# Arduino.net
KiCad netlist of a schematic drawn in Altium Designer
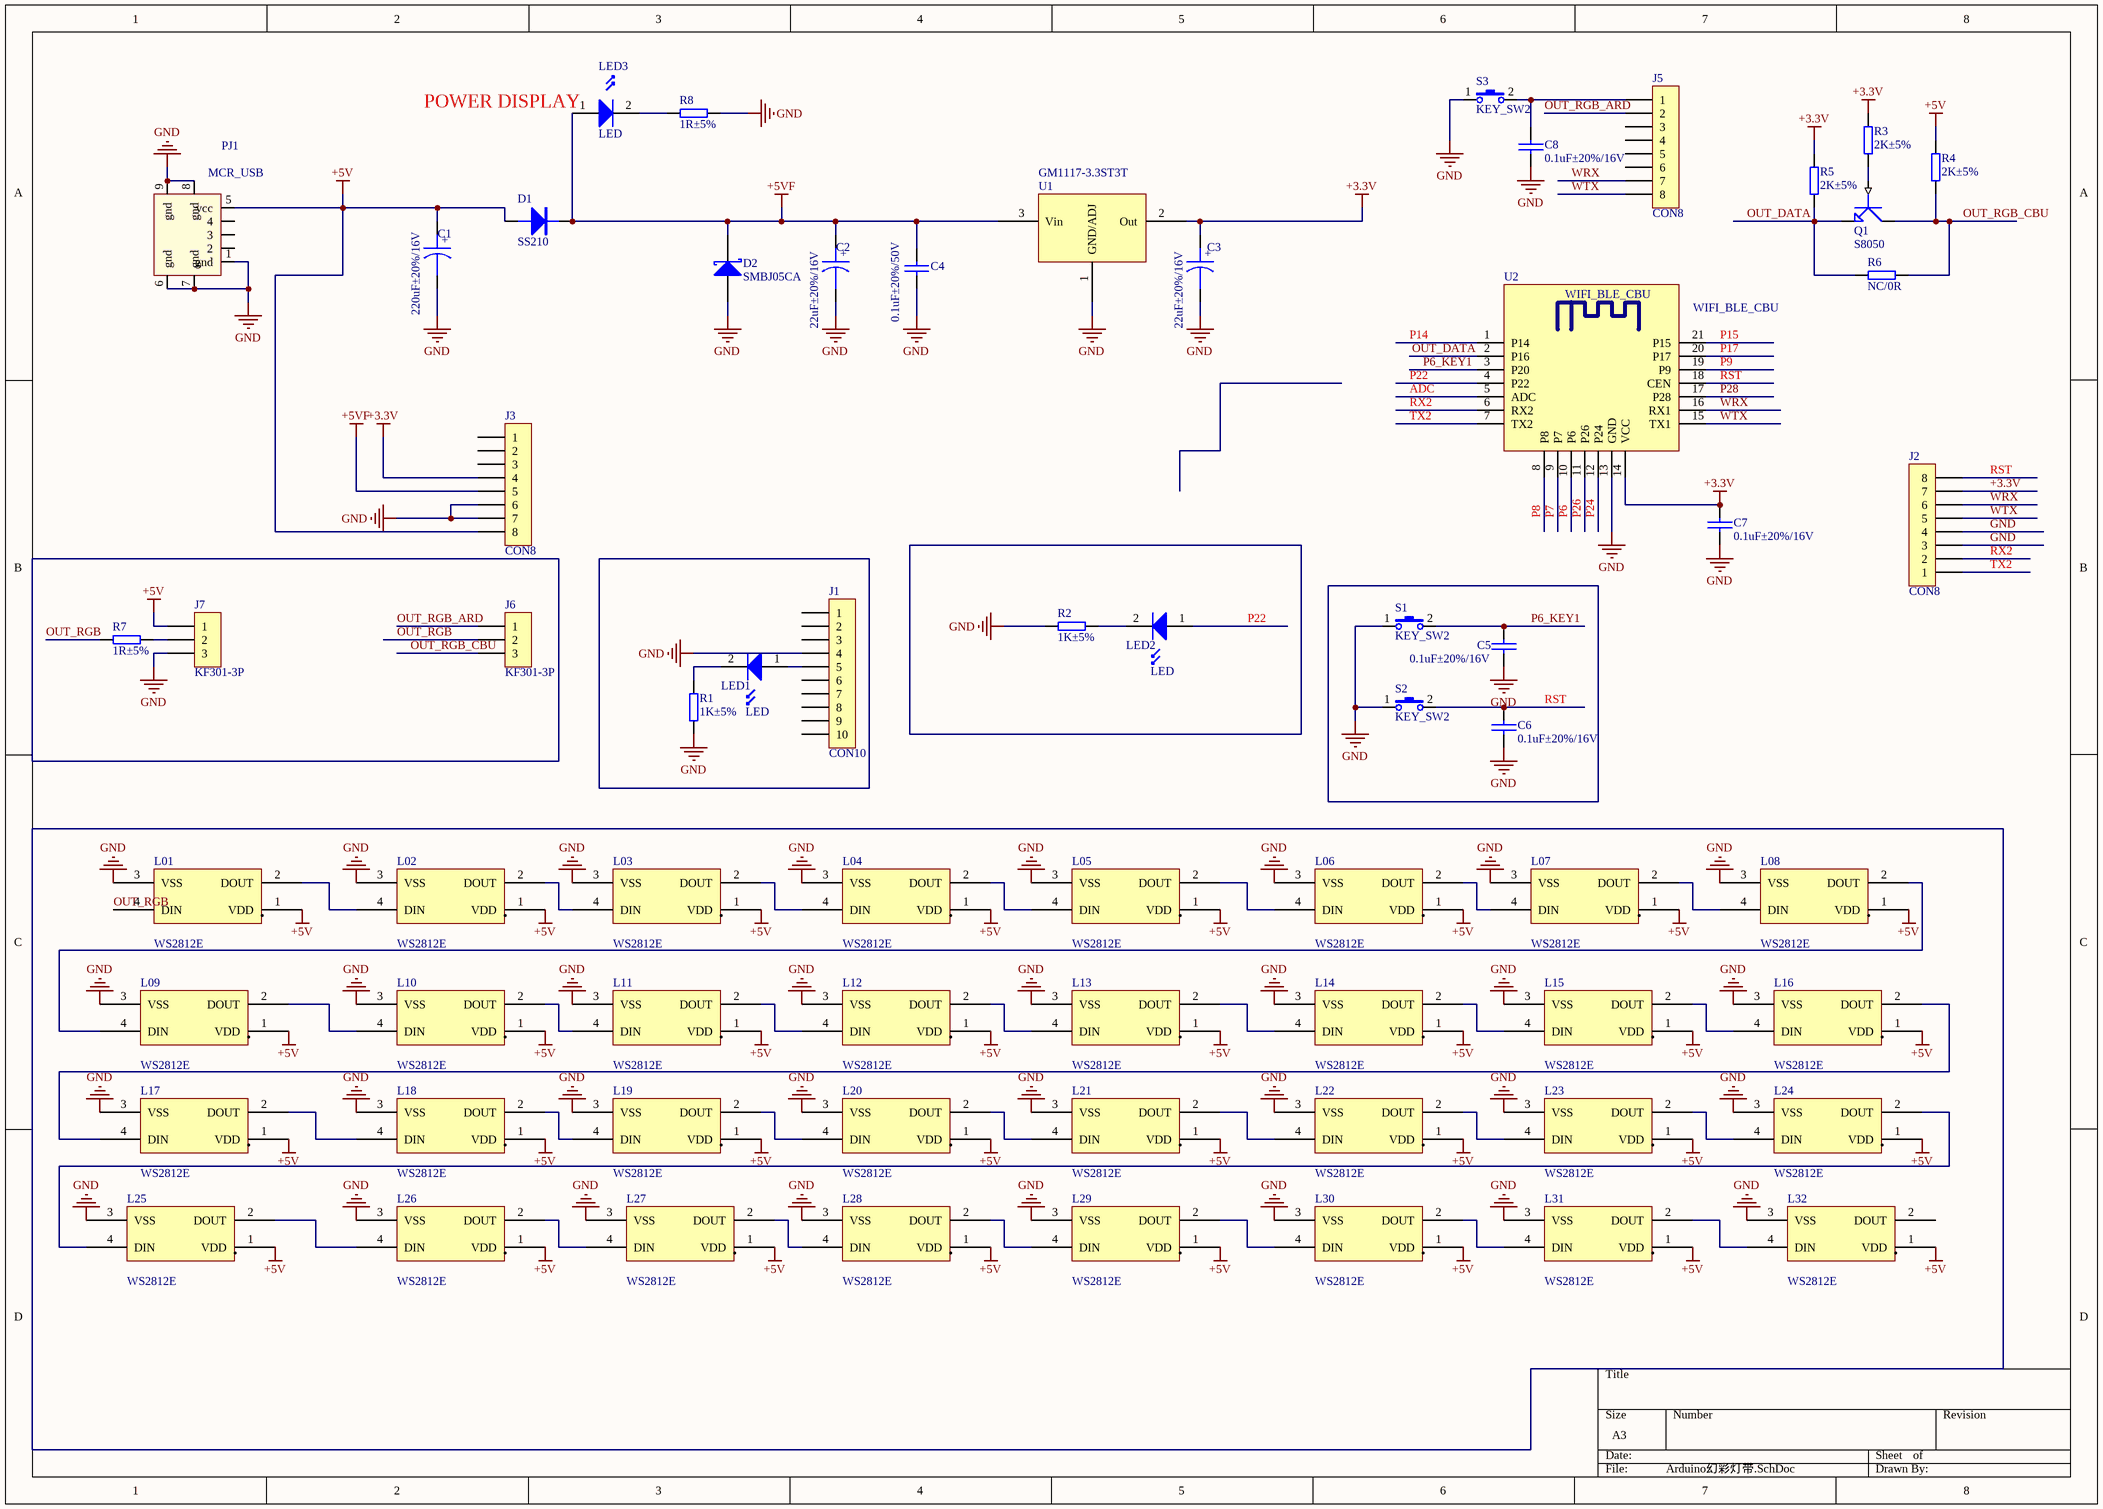
[diagram p0: Arduino幻彩灯带.SchDoc]

(export (version "E")
  (design (tool "Eeschema 10.0.6"))
  (components
    (comp (ref "C1")
      (value "220uF±20%/16V")
      (footprint "钽电容B3528")
      (description "Capacitor")
      (libsource (lib "*") (part "CAPACITOR POL"))
    )
    (comp (ref "C2")
      (value "22uF±20%/16V")
      (footprint "钽电容B3528")
      (description "Capacitor")
      (libsource (lib "*") (part "CAPACITOR POL"))
    )
    (comp (ref "C3")
      (value "22uF±20%/16V")
      (footprint "钽电容B3528")
      (description "Capacitor")
      (libsource (lib "*") (part "CAPACITOR POL"))
    )
    (comp (ref "C4")
      (value "0.1uF±20%/50V")
      (footprint "C0603")
      (description "Capacitor")
      (libsource (lib "昊华元件库sch") (part "CAP"))
    )
    (comp (ref "C5")
      (value "0.1uF±20%/16V")
      (footprint "C0603")
      (description "Capacitor")
      (libsource (lib "昊华元件库sch") (part "CAP"))
    )
    (comp (ref "C6")
      (value "0.1uF±20%/16V")
      (footprint "C0603")
      (description "Capacitor")
      (libsource (lib "昊华元件库sch") (part "CAP"))
    )
    (comp (ref "C7")
      (value "0.1uF±20%/16V")
      (footprint "C0603")
      (description "Capacitor")
      (libsource (lib "昊华元件库sch") (part "CAP"))
    )
    (comp (ref "C8")
      (value "0.1uF±20%/16V")
      (footprint "C0603")
      (description "Capacitor")
      (libsource (lib "昊华元件库sch") (part "CAP"))
    )
    (comp (ref "D1")
      (value "SS210")
      (footprint "SMA(DO-214AC)")
      (description "Diode")
      (libsource (lib "小马元件库sch") (part "Diode1"))
    )
    (comp (ref "D2")
      (value "SMBJ05CA")
      (footprint "SMB(DO-214AA)")
      (description "Schottky Diode")
      (fields (field (name "MFR") "Toshiba"))
      (libsource (lib "Miscellaneous Devices") (part "D Schottky"))
    )
    (comp (ref "J1")
      (value "CON10")
      (footprint "HDR1X10Z")
      (description "Connector")
      (libsource (lib "小马元件库sch") (part "CON10"))
    )
    (comp (ref "J2")
      (value "CON8")
      (footprint "HDR1X8Z")
      (description "Connector")
      (libsource (lib "") (part "CON8_1"))
    )
    (comp (ref "J3")
      (value "CON8")
      (footprint "HDR1X8Z")
      (description "Connector")
      (libsource (lib "小马元件库sch") (part "CON8"))
    )
    (comp (ref "J5")
      (value "CON8")
      (footprint "HDR1X8Z")
      (description "Connector")
      (libsource (lib "小马元件库sch") (part "CON8"))
    )
    (comp (ref "J6")
      (value "KF301-3P")
      (footprint "SIP3 - 2.54")
      (description "Connector")
      (libsource (lib "小马元件库sch") (part "CON3"))
    )
    (comp (ref "J7")
      (value "KF301-3P")
      (footprint "SIP3 - 2.54")
      (description "Connector")
      (libsource (lib "小马元件库sch") (part "CON3"))
    )
    (comp (ref "L01") (value "WS2812E") (footprint "WS2812E") (libsource (lib "WS2812E") (part "WS2812E")))
    (comp (ref "L02") (value "WS2812E") (footprint "WS2812E") (libsource (lib "WS2812E") (part "WS2812E")))
    (comp (ref "L03") (value "WS2812E") (footprint "WS2812E") (libsource (lib "WS2812E") (part "WS2812E")))
    (comp (ref "L04") (value "WS2812E") (footprint "WS2812E") (libsource (lib "WS2812E") (part "WS2812E")))
    (comp (ref "L05") (value "WS2812E") (footprint "WS2812E") (libsource (lib "WS2812E") (part "WS2812E")))
    (comp (ref "L06") (value "WS2812E") (footprint "WS2812E") (libsource (lib "WS2812E") (part "WS2812E")))
    (comp (ref "L07") (value "WS2812E") (footprint "WS2812E") (libsource (lib "WS2812E") (part "WS2812E")))
    (comp (ref "L08") (value "WS2812E") (footprint "WS2812E") (libsource (lib "WS2812E") (part "WS2812E")))
    (comp (ref "L09") (value "WS2812E") (footprint "WS2812E") (libsource (lib "WS2812E") (part "WS2812E")))
    (comp (ref "L10") (value "WS2812E") (footprint "WS2812E") (libsource (lib "WS2812E") (part "WS2812E")))
    (comp (ref "L11") (value "WS2812E") (footprint "WS2812E") (libsource (lib "WS2812E") (part "WS2812E")))
    (comp (ref "L12") (value "WS2812E") (footprint "WS2812E") (libsource (lib "WS2812E") (part "WS2812E")))
    (comp (ref "L13") (value "WS2812E") (footprint "WS2812E") (libsource (lib "WS2812E") (part "WS2812E")))
    (comp (ref "L14") (value "WS2812E") (footprint "WS2812E") (libsource (lib "WS2812E") (part "WS2812E")))
    (comp (ref "L15") (value "WS2812E") (footprint "WS2812E") (libsource (lib "WS2812E") (part "WS2812E")))
    (comp (ref "L16") (value "WS2812E") (footprint "WS2812E") (libsource (lib "WS2812E") (part "WS2812E")))
    (comp (ref "L17") (value "WS2812E") (footprint "WS2812E") (libsource (lib "WS2812E") (part "WS2812E")))
    (comp (ref "L18") (value "WS2812E") (footprint "WS2812E") (libsource (lib "WS2812E") (part "WS2812E")))
    (comp (ref "L19") (value "WS2812E") (footprint "WS2812E") (libsource (lib "WS2812E") (part "WS2812E")))
    (comp (ref "L20") (value "WS2812E") (footprint "WS2812E") (libsource (lib "WS2812E") (part "WS2812E")))
    (comp (ref "L21") (value "WS2812E") (footprint "WS2812E") (libsource (lib "WS2812E") (part "WS2812E")))
    (comp (ref "L22") (value "WS2812E") (footprint "WS2812E") (libsource (lib "WS2812E") (part "WS2812E")))
    (comp (ref "L23") (value "WS2812E") (footprint "WS2812E") (libsource (lib "WS2812E") (part "WS2812E")))
    (comp (ref "L24") (value "WS2812E") (footprint "WS2812E") (libsource (lib "WS2812E") (part "WS2812E")))
    (comp (ref "L25") (value "WS2812E") (footprint "WS2812E") (libsource (lib "WS2812E") (part "WS2812E")))
    (comp (ref "L26") (value "WS2812E") (footprint "WS2812E") (libsource (lib "WS2812E") (part "WS2812E")))
    (comp (ref "L27") (value "WS2812E") (footprint "WS2812E") (libsource (lib "WS2812E") (part "WS2812E")))
    (comp (ref "L28") (value "WS2812E") (footprint "WS2812E") (libsource (lib "WS2812E") (part "WS2812E")))
    (comp (ref "L29") (value "WS2812E") (footprint "WS2812E") (libsource (lib "WS2812E") (part "WS2812E")))
    (comp (ref "L30") (value "WS2812E") (footprint "WS2812E") (libsource (lib "WS2812E") (part "WS2812E")))
    (comp (ref "L31") (value "WS2812E") (footprint "WS2812E") (libsource (lib "WS2812E") (part "WS2812E")))
    (comp (ref "L32") (value "WS2812E") (footprint "WS2812E") (libsource (lib "WS2812E") (part "WS2812E")))
    (comp (ref "LED1")
      (value "LED")
      (footprint "LED0805_1")
      (fields (field (name "PUBLISHER") "*"))
      (libsource (lib "小马元件库sch") (part "LED"))
    )
    (comp (ref "LED2")
      (value "LED")
      (footprint "LED0805_1")
      (fields (field (name "PUBLISHER") "*"))
      (libsource (lib "小马元件库sch") (part "LED"))
    )
    (comp (ref "LED3")
      (value "LED")
      (footprint "LED0805_1")
      (fields (field (name "PUBLISHER") "*"))
      (libsource (lib "小马元件库sch") (part "LED"))
    )
    (comp (ref "PJ1")
      (value "MCR_USB")
      (footprint "MICRO_USB-NEW-16.12.12")
      (fields (field (name "PUBLISHER") "*"))
      (libsource (lib "昊华元件库sch") (part "MCR_USB"))
    )
    (comp (ref "Q1")
      (value "S8050")
      (footprint "SOT-23-NPN")
      (description "NPN Transistor")
      (libsource (lib "小马元件库sch") (part "NPN"))
    )
    (comp (ref "R1") (value "1K±5%") (footprint "R0603") (libsource (lib "昊华元件库sch") (part "RES5")))
    (comp (ref "R2") (value "1K±5%") (footprint "R0603") (libsource (lib "昊华元件库sch") (part "RES5")))
    (comp (ref "R3") (value "2K±5%") (footprint "R0603") (libsource (lib "昊华元件库sch") (part "RES5")))
    (comp (ref "R4") (value "2K±5%") (footprint "R0603") (libsource (lib "昊华元件库sch") (part "RES5")))
    (comp (ref "R5") (value "2K±5%") (footprint "R0603") (libsource (lib "昊华元件库sch") (part "RES5")))
    (comp (ref "R6") (value "NC/0R") (footprint "R0603") (libsource (lib "昊华元件库sch") (part "RES5")))
    (comp (ref "R7") (value "1R±5%") (footprint "R0603") (libsource (lib "昊华元件库sch") (part "RES5")))
    (comp (ref "R8") (value "1R±5%") (footprint "R0603") (libsource (lib "昊华元件库sch") (part "RES5")))
    (comp (ref "S1") (value "KEY_SW2") (footprint "KEY4-SMD") (libsource (lib "小马元件库sch") (part "KEY_SW2")))
    (comp (ref "S2") (value "KEY_SW2") (footprint "KEY4-SMD") (libsource (lib "小马元件库sch") (part "KEY_SW2")))
    (comp (ref "S3") (value "KEY_SW2") (footprint "KEY4-SMD") (libsource (lib "小马元件库sch") (part "KEY_SW2")))
    (comp (ref "U1") (value "GM1117-3.3ST3T") (footprint "SOT-223") (libsource (lib "mylib") (part "GM1117")))
    (comp (ref "U2")
      (value "WIFI_BLE_CBU")
      (footprint "WIFI_BLE_CBU")
      (description "Module")
      (libsource (lib "TYModeSchlib V03") (part "WIFI_BLE_CBU"))
    )
  )
  (nets
    (net (code "1") (name "+3.3V") (class "Default")
      (node (ref "C3") (pin "1") (pinfunction "1_1") (pintype "passive"))
      (node (ref "C7") (pin "2") (pinfunction "2_2") (pintype "passive"))
      (node (ref "J2") (pin "7") (pinfunction "7_7") (pintype "passive"))
      (node (ref "J3") (pin "4") (pinfunction "4_4") (pintype "passive"))
      (node (ref "R3") (pin "1") (pinfunction "1_1") (pintype "passive"))
      (node (ref "R5") (pin "1") (pinfunction "1_1") (pintype "passive"))
      (node (ref "U1") (pin "2") (pinfunction "Out_2") (pintype "passive"))
      (node (ref "U2") (pin "14") (pinfunction "VCC_14") (pintype "passive"))
    )
    (net (code "2") (name "+5V") (class "Default")
      (node (ref "C1") (pin "1") (pinfunction "1_1") (pintype "passive"))
      (node (ref "D1") (pin "1") (pinfunction "1_1") (pintype "passive"))
      (node (ref "J3") (pin "8") (pinfunction "8_8") (pintype "passive"))
      (node (ref "J7") (pin "1") (pinfunction "1_1") (pintype "passive"))
      (node (ref "L01") (pin "1") (pinfunction "VDD_1") (pintype "passive"))
      (node (ref "L02") (pin "1") (pinfunction "VDD_1") (pintype "passive"))
      (node (ref "L03") (pin "1") (pinfunction "VDD_1") (pintype "passive"))
      (node (ref "L04") (pin "1") (pinfunction "VDD_1") (pintype "passive"))
      (node (ref "L05") (pin "1") (pinfunction "VDD_1") (pintype "passive"))
      (node (ref "L06") (pin "1") (pinfunction "VDD_1") (pintype "passive"))
      (node (ref "L07") (pin "1") (pinfunction "VDD_1") (pintype "passive"))
      (node (ref "L08") (pin "1") (pinfunction "VDD_1") (pintype "passive"))
      (node (ref "L09") (pin "1") (pinfunction "VDD_1") (pintype "passive"))
      (node (ref "L10") (pin "1") (pinfunction "VDD_1") (pintype "passive"))
      (node (ref "L11") (pin "1") (pinfunction "VDD_1") (pintype "passive"))
      (node (ref "L12") (pin "1") (pinfunction "VDD_1") (pintype "passive"))
      (node (ref "L13") (pin "1") (pinfunction "VDD_1") (pintype "passive"))
      (node (ref "L14") (pin "1") (pinfunction "VDD_1") (pintype "passive"))
      (node (ref "L15") (pin "1") (pinfunction "VDD_1") (pintype "passive"))
      (node (ref "L16") (pin "1") (pinfunction "VDD_1") (pintype "passive"))
      (node (ref "L17") (pin "1") (pinfunction "VDD_1") (pintype "passive"))
      (node (ref "L18") (pin "1") (pinfunction "VDD_1") (pintype "passive"))
      (node (ref "L19") (pin "1") (pinfunction "VDD_1") (pintype "passive"))
      (node (ref "L20") (pin "1") (pinfunction "VDD_1") (pintype "passive"))
      (node (ref "L21") (pin "1") (pinfunction "VDD_1") (pintype "passive"))
      (node (ref "L22") (pin "1") (pinfunction "VDD_1") (pintype "passive"))
      (node (ref "L23") (pin "1") (pinfunction "VDD_1") (pintype "passive"))
      (node (ref "L24") (pin "1") (pinfunction "VDD_1") (pintype "passive"))
      (node (ref "L25") (pin "1") (pinfunction "VDD_1") (pintype "passive"))
      (node (ref "L26") (pin "1") (pinfunction "VDD_1") (pintype "passive"))
      (node (ref "L27") (pin "1") (pinfunction "VDD_1") (pintype "passive"))
      (node (ref "L28") (pin "1") (pinfunction "VDD_1") (pintype "passive"))
      (node (ref "L29") (pin "1") (pinfunction "VDD_1") (pintype "passive"))
      (node (ref "L30") (pin "1") (pinfunction "VDD_1") (pintype "passive"))
      (node (ref "L31") (pin "1") (pinfunction "VDD_1") (pintype "passive"))
      (node (ref "L32") (pin "1") (pinfunction "VDD_1") (pintype "passive"))
      (node (ref "PJ1") (pin "5") (pinfunction "vcc_5") (pintype "passive"))
      (node (ref "R4") (pin "1") (pinfunction "1_1") (pintype "passive"))
    )
    (net (code "3") (name "+5VF") (class "Default")
      (node (ref "C2") (pin "1") (pinfunction "1_1") (pintype "passive"))
      (node (ref "C4") (pin "1") (pinfunction "1_1") (pintype "passive"))
      (node (ref "D1") (pin "2") (pinfunction "2_2") (pintype "passive"))
      (node (ref "D2") (pin "2") (pinfunction "K_2") (pintype "passive"))
      (node (ref "J3") (pin "5") (pinfunction "5_5") (pintype "passive"))
      (node (ref "LED3") (pin "1") (pinfunction "1_1") (pintype "passive"))
      (node (ref "U1") (pin "3") (pinfunction "Vin_3") (pintype "passive"))
    )
    (net (code "4") (name "/ADC") (class "Default")
      (node (ref "U2") (pin "5") (pinfunction "ADC_5") (pintype "passive"))
    )
    (net (code "5") (name "/OUT_DATA") (class "Default")
      (node (ref "Q1") (pin "1") (pinfunction "E_1") (pintype "passive"))
      (node (ref "R5") (pin "2") (pinfunction "2_2") (pintype "passive"))
      (node (ref "R6") (pin "1") (pinfunction "1_1") (pintype "passive"))
      (node (ref "U2") (pin "2") (pinfunction "P16_2") (pintype "passive"))
    )
    (net (code "6") (name "/OUT_RGB") (class "Default")
      (node (ref "J6") (pin "2") (pinfunction "2_2") (pintype "passive"))
      (node (ref "L01") (pin "4") (pinfunction "DIN_4") (pintype "passive"))
      (node (ref "R7") (pin "1") (pinfunction "1_1") (pintype "passive"))
    )
    (net (code "7") (name "/OUT_RGB_ARD") (class "Default")
      (node (ref "J5") (pin "2") (pinfunction "2_2") (pintype "passive"))
      (node (ref "J6") (pin "1") (pinfunction "1_1") (pintype "passive"))
    )
    (net (code "8") (name "/OUT_RGB_CBU") (class "Default")
      (node (ref "J6") (pin "3") (pinfunction "3_3") (pintype "passive"))
      (node (ref "Q1") (pin "3") (pinfunction "C_3") (pintype "passive"))
      (node (ref "R4") (pin "2") (pinfunction "2_2") (pintype "passive"))
      (node (ref "R6") (pin "2") (pinfunction "2_2") (pintype "passive"))
    )
    (net (code "9") (name "/P6") (class "Default")
      (node (ref "U2") (pin "10") (pinfunction "P6_10") (pintype "passive"))
    )
    (net (code "10") (name "/P6_KEY1") (class "Default")
      (node (ref "C5") (pin "2") (pinfunction "2_2") (pintype "passive"))
      (node (ref "S1") (pin "2") (pinfunction "2_2") (pintype "passive"))
      (node (ref "U2") (pin "3") (pinfunction "P20_3") (pintype "passive"))
    )
    (net (code "11") (name "/P7") (class "Default")
      (node (ref "U2") (pin "9") (pinfunction "P7_9") (pintype "passive"))
    )
    (net (code "12") (name "/P8") (class "Default")
      (node (ref "U2") (pin "8") (pinfunction "P8_8") (pintype "passive"))
    )
    (net (code "13") (name "/P9") (class "Default")
      (node (ref "U2") (pin "19") (pinfunction "P9_19") (pintype "passive"))
    )
    (net (code "14") (name "/P14") (class "Default")
      (node (ref "U2") (pin "1") (pinfunction "P14_1") (pintype "passive"))
    )
    (net (code "15") (name "/P15") (class "Default")
      (node (ref "U2") (pin "21") (pinfunction "P15_21") (pintype "passive"))
    )
    (net (code "16") (name "/P17") (class "Default")
      (node (ref "U2") (pin "20") (pinfunction "P17_20") (pintype "passive"))
    )
    (net (code "17") (name "/P22") (class "Default")
      (node (ref "LED2") (pin "1") (pinfunction "1_1") (pintype "passive"))
      (node (ref "U2") (pin "4") (pinfunction "P22_4") (pintype "passive"))
    )
    (net (code "18") (name "/P24") (class "Default")
      (node (ref "U2") (pin "12") (pinfunction "P24_12") (pintype "passive"))
    )
    (net (code "19") (name "/P26") (class "Default")
      (node (ref "U2") (pin "11") (pinfunction "P26_11") (pintype "passive"))
    )
    (net (code "20") (name "/P28") (class "Default")
      (node (ref "U2") (pin "17") (pinfunction "P28_17") (pintype "passive"))
    )
    (net (code "21") (name "/RST") (class "Default")
      (node (ref "C6") (pin "1") (pinfunction "1_1") (pintype "passive"))
      (node (ref "J2") (pin "8") (pinfunction "8_8") (pintype "passive"))
      (node (ref "S2") (pin "2") (pinfunction "2_2") (pintype "passive"))
      (node (ref "U2") (pin "18") (pinfunction "CEN_18") (pintype "passive"))
    )
    (net (code "22") (name "/RX2") (class "Default")
      (node (ref "J2") (pin "2") (pinfunction "2_2") (pintype "passive"))
      (node (ref "U2") (pin "6") (pinfunction "RX2_6") (pintype "passive"))
    )
    (net (code "23") (name "/TX2") (class "Default")
      (node (ref "J2") (pin "1") (pinfunction "1_1") (pintype "passive"))
      (node (ref "U2") (pin "7") (pinfunction "TX2_7") (pintype "passive"))
    )
    (net (code "24") (name "/WRX") (class "Default")
      (node (ref "J2") (pin "6") (pinfunction "6_6") (pintype "passive"))
      (node (ref "J5") (pin "7") (pinfunction "7_7") (pintype "passive"))
      (node (ref "U2") (pin "16") (pinfunction "RX1_16") (pintype "passive"))
    )
    (net (code "25") (name "/WTX") (class "Default")
      (node (ref "J2") (pin "5") (pinfunction "5_5") (pintype "passive"))
      (node (ref "J5") (pin "8") (pinfunction "8_8") (pintype "passive"))
      (node (ref "U2") (pin "15") (pinfunction "TX1_15") (pintype "passive"))
    )
    (net (code "26") (name "GND") (class "Default")
      (node (ref "C1") (pin "2") (pinfunction "2_2") (pintype "passive"))
      (node (ref "C2") (pin "2") (pinfunction "2_2") (pintype "passive"))
      (node (ref "C3") (pin "2") (pinfunction "2_2") (pintype "passive"))
      (node (ref "C4") (pin "2") (pinfunction "2_2") (pintype "passive"))
      (node (ref "C5") (pin "1") (pinfunction "1_1") (pintype "passive"))
      (node (ref "C6") (pin "2") (pinfunction "2_2") (pintype "passive"))
      (node (ref "C7") (pin "1") (pinfunction "1_1") (pintype "passive"))
      (node (ref "C8") (pin "1") (pinfunction "1_1") (pintype "passive"))
      (node (ref "D2") (pin "1") (pinfunction "A_1") (pintype "passive"))
      (node (ref "J1") (pin "4") (pinfunction "4_4") (pintype "passive"))
      (node (ref "J2") (pin "3") (pinfunction "3_3") (pintype "passive"))
      (node (ref "J2") (pin "4") (pinfunction "4_4") (pintype "passive"))
      (node (ref "J3") (pin "6") (pinfunction "6_6") (pintype "passive"))
      (node (ref "J3") (pin "7") (pinfunction "7_7") (pintype "passive"))
      (node (ref "J7") (pin "3") (pinfunction "3_3") (pintype "passive"))
      (node (ref "L01") (pin "3") (pinfunction "VSS_3") (pintype "passive"))
      (node (ref "L02") (pin "3") (pinfunction "VSS_3") (pintype "passive"))
      (node (ref "L03") (pin "3") (pinfunction "VSS_3") (pintype "passive"))
      (node (ref "L04") (pin "3") (pinfunction "VSS_3") (pintype "passive"))
      (node (ref "L05") (pin "3") (pinfunction "VSS_3") (pintype "passive"))
      (node (ref "L06") (pin "3") (pinfunction "VSS_3") (pintype "passive"))
      (node (ref "L07") (pin "3") (pinfunction "VSS_3") (pintype "passive"))
      (node (ref "L08") (pin "3") (pinfunction "VSS_3") (pintype "passive"))
      (node (ref "L09") (pin "3") (pinfunction "VSS_3") (pintype "passive"))
      (node (ref "L10") (pin "3") (pinfunction "VSS_3") (pintype "passive"))
      (node (ref "L11") (pin "3") (pinfunction "VSS_3") (pintype "passive"))
      (node (ref "L12") (pin "3") (pinfunction "VSS_3") (pintype "passive"))
      (node (ref "L13") (pin "3") (pinfunction "VSS_3") (pintype "passive"))
      (node (ref "L14") (pin "3") (pinfunction "VSS_3") (pintype "passive"))
      (node (ref "L15") (pin "3") (pinfunction "VSS_3") (pintype "passive"))
      (node (ref "L16") (pin "3") (pinfunction "VSS_3") (pintype "passive"))
      (node (ref "L17") (pin "3") (pinfunction "VSS_3") (pintype "passive"))
      (node (ref "L18") (pin "3") (pinfunction "VSS_3") (pintype "passive"))
      (node (ref "L19") (pin "3") (pinfunction "VSS_3") (pintype "passive"))
      (node (ref "L20") (pin "3") (pinfunction "VSS_3") (pintype "passive"))
      (node (ref "L21") (pin "3") (pinfunction "VSS_3") (pintype "passive"))
      (node (ref "L22") (pin "3") (pinfunction "VSS_3") (pintype "passive"))
      (node (ref "L23") (pin "3") (pinfunction "VSS_3") (pintype "passive"))
      (node (ref "L24") (pin "3") (pinfunction "VSS_3") (pintype "passive"))
      (node (ref "L25") (pin "3") (pinfunction "VSS_3") (pintype "passive"))
      (node (ref "L26") (pin "3") (pinfunction "VSS_3") (pintype "passive"))
      (node (ref "L27") (pin "3") (pinfunction "VSS_3") (pintype "passive"))
      (node (ref "L28") (pin "3") (pinfunction "VSS_3") (pintype "passive"))
      (node (ref "L29") (pin "3") (pinfunction "VSS_3") (pintype "passive"))
      (node (ref "L30") (pin "3") (pinfunction "VSS_3") (pintype "passive"))
      (node (ref "L31") (pin "3") (pinfunction "VSS_3") (pintype "passive"))
      (node (ref "L32") (pin "3") (pinfunction "VSS_3") (pintype "passive"))
      (node (ref "PJ1") (pin "1") (pinfunction "gnd_1") (pintype "passive"))
      (node (ref "PJ1") (pin "6") (pinfunction "gnd_6") (pintype "passive"))
      (node (ref "PJ1") (pin "7") (pinfunction "gnd_7") (pintype "passive"))
      (node (ref "PJ1") (pin "8") (pinfunction "gnd_8") (pintype "passive"))
      (node (ref "PJ1") (pin "9") (pinfunction "gnd_9") (pintype "passive"))
      (node (ref "R1") (pin "1") (pinfunction "1_1") (pintype "passive"))
      (node (ref "R2") (pin "2") (pinfunction "2_2") (pintype "passive"))
      (node (ref "R8") (pin "2") (pinfunction "2_2") (pintype "passive"))
      (node (ref "S1") (pin "1") (pinfunction "1_1") (pintype "passive"))
      (node (ref "S2") (pin "1") (pinfunction "1_1") (pintype "passive"))
      (node (ref "S3") (pin "1") (pinfunction "1_1") (pintype "passive"))
      (node (ref "U1") (pin "1") (pinfunction "GND/ADJ_1") (pintype "passive"))
      (node (ref "U2") (pin "13") (pinfunction "GND_13") (pintype "passive"))
    )
    (net (code "27") (name "Net-(C8-Pad2)") (class "Default")
      (node (ref "C8") (pin "2") (pinfunction "2_2") (pintype "passive"))
      (node (ref "J5") (pin "1") (pinfunction "1_1") (pintype "passive"))
      (node (ref "S3") (pin "2") (pinfunction "2_2") (pintype "passive"))
    )
    (net (code "28") (name "Net-(J1-Pad5)") (class "Default")
      (node (ref "J1") (pin "5") (pinfunction "5_5") (pintype "passive"))
      (node (ref "LED1") (pin "1") (pinfunction "1_1") (pintype "passive"))
    )
    (net (code "29") (name "Net-(J7-Pad2)") (class "Default")
      (node (ref "J7") (pin "2") (pinfunction "2_2") (pintype "passive"))
      (node (ref "R7") (pin "2") (pinfunction "2_2") (pintype "passive"))
    )
    (net (code "30") (name "Net-(L01-DOUT)") (class "Default")
      (node (ref "L01") (pin "2") (pinfunction "DOUT_2") (pintype "passive"))
      (node (ref "L02") (pin "4") (pinfunction "DIN_4") (pintype "passive"))
    )
    (net (code "31") (name "Net-(L02-DOUT)") (class "Default")
      (node (ref "L02") (pin "2") (pinfunction "DOUT_2") (pintype "passive"))
      (node (ref "L03") (pin "4") (pinfunction "DIN_4") (pintype "passive"))
    )
    (net (code "32") (name "Net-(L03-DOUT)") (class "Default")
      (node (ref "L03") (pin "2") (pinfunction "DOUT_2") (pintype "passive"))
      (node (ref "L04") (pin "4") (pinfunction "DIN_4") (pintype "passive"))
    )
    (net (code "33") (name "Net-(L04-DOUT)") (class "Default")
      (node (ref "L04") (pin "2") (pinfunction "DOUT_2") (pintype "passive"))
      (node (ref "L05") (pin "4") (pinfunction "DIN_4") (pintype "passive"))
    )
    (net (code "34") (name "Net-(L05-DOUT)") (class "Default")
      (node (ref "L05") (pin "2") (pinfunction "DOUT_2") (pintype "passive"))
      (node (ref "L06") (pin "4") (pinfunction "DIN_4") (pintype "passive"))
    )
    (net (code "35") (name "Net-(L06-DOUT)") (class "Default")
      (node (ref "L06") (pin "2") (pinfunction "DOUT_2") (pintype "passive"))
      (node (ref "L07") (pin "4") (pinfunction "DIN_4") (pintype "passive"))
    )
    (net (code "36") (name "Net-(L07-DOUT)") (class "Default")
      (node (ref "L07") (pin "2") (pinfunction "DOUT_2") (pintype "passive"))
      (node (ref "L08") (pin "4") (pinfunction "DIN_4") (pintype "passive"))
    )
    (net (code "37") (name "Net-(L08-DOUT)") (class "Default")
      (node (ref "L08") (pin "2") (pinfunction "DOUT_2") (pintype "passive"))
      (node (ref "L09") (pin "4") (pinfunction "DIN_4") (pintype "passive"))
    )
    (net (code "38") (name "Net-(L09-DOUT)") (class "Default")
      (node (ref "L09") (pin "2") (pinfunction "DOUT_2") (pintype "passive"))
      (node (ref "L10") (pin "4") (pinfunction "DIN_4") (pintype "passive"))
    )
    (net (code "39") (name "Net-(L10-DOUT)") (class "Default")
      (node (ref "L10") (pin "2") (pinfunction "DOUT_2") (pintype "passive"))
      (node (ref "L11") (pin "4") (pinfunction "DIN_4") (pintype "passive"))
    )
    (net (code "40") (name "Net-(L11-DOUT)") (class "Default")
      (node (ref "L11") (pin "2") (pinfunction "DOUT_2") (pintype "passive"))
      (node (ref "L12") (pin "4") (pinfunction "DIN_4") (pintype "passive"))
    )
    (net (code "41") (name "Net-(L12-DOUT)") (class "Default")
      (node (ref "L12") (pin "2") (pinfunction "DOUT_2") (pintype "passive"))
      (node (ref "L13") (pin "4") (pinfunction "DIN_4") (pintype "passive"))
    )
    (net (code "42") (name "Net-(L13-DOUT)") (class "Default")
      (node (ref "L13") (pin "2") (pinfunction "DOUT_2") (pintype "passive"))
      (node (ref "L14") (pin "4") (pinfunction "DIN_4") (pintype "passive"))
    )
    (net (code "43") (name "Net-(L14-DOUT)") (class "Default")
      (node (ref "L14") (pin "2") (pinfunction "DOUT_2") (pintype "passive"))
      (node (ref "L15") (pin "4") (pinfunction "DIN_4") (pintype "passive"))
    )
    (net (code "44") (name "Net-(L15-DOUT)") (class "Default")
      (node (ref "L15") (pin "2") (pinfunction "DOUT_2") (pintype "passive"))
      (node (ref "L16") (pin "4") (pinfunction "DIN_4") (pintype "passive"))
    )
    (net (code "45") (name "Net-(L16-DOUT)") (class "Default")
      (node (ref "L16") (pin "2") (pinfunction "DOUT_2") (pintype "passive"))
      (node (ref "L17") (pin "4") (pinfunction "DIN_4") (pintype "passive"))
    )
    (net (code "46") (name "Net-(L17-DOUT)") (class "Default")
      (node (ref "L17") (pin "2") (pinfunction "DOUT_2") (pintype "passive"))
      (node (ref "L18") (pin "4") (pinfunction "DIN_4") (pintype "passive"))
    )
    (net (code "47") (name "Net-(L18-DOUT)") (class "Default")
      (node (ref "L18") (pin "2") (pinfunction "DOUT_2") (pintype "passive"))
      (node (ref "L19") (pin "4") (pinfunction "DIN_4") (pintype "passive"))
    )
    (net (code "48") (name "Net-(L19-DOUT)") (class "Default")
      (node (ref "L19") (pin "2") (pinfunction "DOUT_2") (pintype "passive"))
      (node (ref "L20") (pin "4") (pinfunction "DIN_4") (pintype "passive"))
    )
    (net (code "49") (name "Net-(L20-DOUT)") (class "Default")
      (node (ref "L20") (pin "2") (pinfunction "DOUT_2") (pintype "passive"))
      (node (ref "L21") (pin "4") (pinfunction "DIN_4") (pintype "passive"))
    )
    (net (code "50") (name "Net-(L21-DOUT)") (class "Default")
      (node (ref "L21") (pin "2") (pinfunction "DOUT_2") (pintype "passive"))
      (node (ref "L22") (pin "4") (pinfunction "DIN_4") (pintype "passive"))
    )
    (net (code "51") (name "Net-(L22-DOUT)") (class "Default")
      (node (ref "L22") (pin "2") (pinfunction "DOUT_2") (pintype "passive"))
      (node (ref "L23") (pin "4") (pinfunction "DIN_4") (pintype "passive"))
    )
    (net (code "52") (name "Net-(L23-DOUT)") (class "Default")
      (node (ref "L23") (pin "2") (pinfunction "DOUT_2") (pintype "passive"))
      (node (ref "L24") (pin "4") (pinfunction "DIN_4") (pintype "passive"))
    )
    (net (code "53") (name "Net-(L24-DOUT)") (class "Default")
      (node (ref "L24") (pin "2") (pinfunction "DOUT_2") (pintype "passive"))
      (node (ref "L25") (pin "4") (pinfunction "DIN_4") (pintype "passive"))
    )
    (net (code "54") (name "Net-(L25-DOUT)") (class "Default")
      (node (ref "L25") (pin "2") (pinfunction "DOUT_2") (pintype "passive"))
      (node (ref "L26") (pin "4") (pinfunction "DIN_4") (pintype "passive"))
    )
    (net (code "55") (name "Net-(L26-DOUT)") (class "Default")
      (node (ref "L26") (pin "2") (pinfunction "DOUT_2") (pintype "passive"))
      (node (ref "L27") (pin "4") (pinfunction "DIN_4") (pintype "passive"))
    )
    (net (code "56") (name "Net-(L27-DOUT)") (class "Default")
      (node (ref "L27") (pin "2") (pinfunction "DOUT_2") (pintype "passive"))
      (node (ref "L28") (pin "4") (pinfunction "DIN_4") (pintype "passive"))
    )
    (net (code "57") (name "Net-(L28-DOUT)") (class "Default")
      (node (ref "L28") (pin "2") (pinfunction "DOUT_2") (pintype "passive"))
      (node (ref "L29") (pin "4") (pinfunction "DIN_4") (pintype "passive"))
    )
    (net (code "58") (name "Net-(L29-DOUT)") (class "Default")
      (node (ref "L29") (pin "2") (pinfunction "DOUT_2") (pintype "passive"))
      (node (ref "L30") (pin "4") (pinfunction "DIN_4") (pintype "passive"))
    )
    (net (code "59") (name "Net-(L30-DOUT)") (class "Default")
      (node (ref "L30") (pin "2") (pinfunction "DOUT_2") (pintype "passive"))
      (node (ref "L31") (pin "4") (pinfunction "DIN_4") (pintype "passive"))
    )
    (net (code "60") (name "Net-(L31-DOUT)") (class "Default")
      (node (ref "L31") (pin "2") (pinfunction "DOUT_2") (pintype "passive"))
      (node (ref "L32") (pin "4") (pinfunction "DIN_4") (pintype "passive"))
    )
    (net (code "61") (name "Net-(LED1-Pad2)") (class "Default")
      (node (ref "LED1") (pin "2") (pinfunction "2_2") (pintype "passive"))
      (node (ref "R1") (pin "2") (pinfunction "2_2") (pintype "passive"))
    )
    (net (code "62") (name "Net-(LED2-Pad2)") (class "Default")
      (node (ref "LED2") (pin "2") (pinfunction "2_2") (pintype "passive"))
      (node (ref "R2") (pin "1") (pinfunction "1_1") (pintype "passive"))
    )
    (net (code "63") (name "Net-(LED3-Pad2)") (class "Default")
      (node (ref "LED3") (pin "2") (pinfunction "2_2") (pintype "passive"))
      (node (ref "R8") (pin "1") (pinfunction "1_1") (pintype "passive"))
    )
    (net (code "64") (name "Net-(Q1-B)") (class "Default")
      (node (ref "Q1") (pin "2") (pinfunction "B_2") (pintype "input"))
      (node (ref "R3") (pin "2") (pinfunction "2_2") (pintype "passive"))
    )
    (net (code "65") (name "unconnected-(J1-Pad1)") (class "Default")
      (node (ref "J1") (pin "1") (pinfunction "1_1") (pintype "passive"))
    )
    (net (code "66") (name "unconnected-(J1-Pad2)") (class "Default")
      (node (ref "J1") (pin "2") (pinfunction "2_2") (pintype "passive"))
    )
    (net (code "67") (name "unconnected-(J1-Pad3)") (class "Default")
      (node (ref "J1") (pin "3") (pinfunction "3_3") (pintype "passive"))
    )
    (net (code "68") (name "unconnected-(J1-Pad6)") (class "Default")
      (node (ref "J1") (pin "6") (pinfunction "6_6") (pintype "passive"))
    )
    (net (code "69") (name "unconnected-(J1-Pad7)") (class "Default")
      (node (ref "J1") (pin "7") (pinfunction "7_7") (pintype "passive"))
    )
    (net (code "70") (name "unconnected-(J1-Pad8)") (class "Default")
      (node (ref "J1") (pin "8") (pinfunction "8_8") (pintype "passive"))
    )
    (net (code "71") (name "unconnected-(J1-Pad9)") (class "Default")
      (node (ref "J1") (pin "9") (pinfunction "9_9") (pintype "passive"))
    )
    (net (code "72") (name "unconnected-(J1-Pad10)") (class "Default")
      (node (ref "J1") (pin "10") (pinfunction "10_10") (pintype "passive"))
    )
    (net (code "73") (name "unconnected-(J3-Pad1)") (class "Default")
      (node (ref "J3") (pin "1") (pinfunction "1_1") (pintype "passive"))
    )
    (net (code "74") (name "unconnected-(J3-Pad2)") (class "Default")
      (node (ref "J3") (pin "2") (pinfunction "2_2") (pintype "passive"))
    )
    (net (code "75") (name "unconnected-(J3-Pad3)") (class "Default")
      (node (ref "J3") (pin "3") (pinfunction "3_3") (pintype "passive"))
    )
    (net (code "76") (name "unconnected-(J5-Pad3)") (class "Default")
      (node (ref "J5") (pin "3") (pinfunction "3_3") (pintype "passive"))
    )
    (net (code "77") (name "unconnected-(J5-Pad4)") (class "Default")
      (node (ref "J5") (pin "4") (pinfunction "4_4") (pintype "passive"))
    )
    (net (code "78") (name "unconnected-(J5-Pad5)") (class "Default")
      (node (ref "J5") (pin "5") (pinfunction "5_5") (pintype "passive"))
    )
    (net (code "79") (name "unconnected-(J5-Pad6)") (class "Default")
      (node (ref "J5") (pin "6") (pinfunction "6_6") (pintype "passive"))
    )
    (net (code "80") (name "unconnected-(L32-DOUT-Pad2)") (class "Default")
      (node (ref "L32") (pin "2") (pinfunction "DOUT_2") (pintype "passive"))
    )
    (net (code "81") (name "unconnected-(PJ1-Pad2)") (class "Default")
      (node (ref "PJ1") (pin "2") (pinfunction "2_2") (pintype "passive"))
    )
    (net (code "82") (name "unconnected-(PJ1-Pad3)") (class "Default")
      (node (ref "PJ1") (pin "3") (pinfunction "3_3") (pintype "passive"))
    )
    (net (code "83") (name "unconnected-(PJ1-Pad4)") (class "Default")
      (node (ref "PJ1") (pin "4") (pinfunction "4_4") (pintype "passive"))
    )
  )
)
